# esquema-receptor.net
KiCad netlist of a schematic drawn in EAGLE
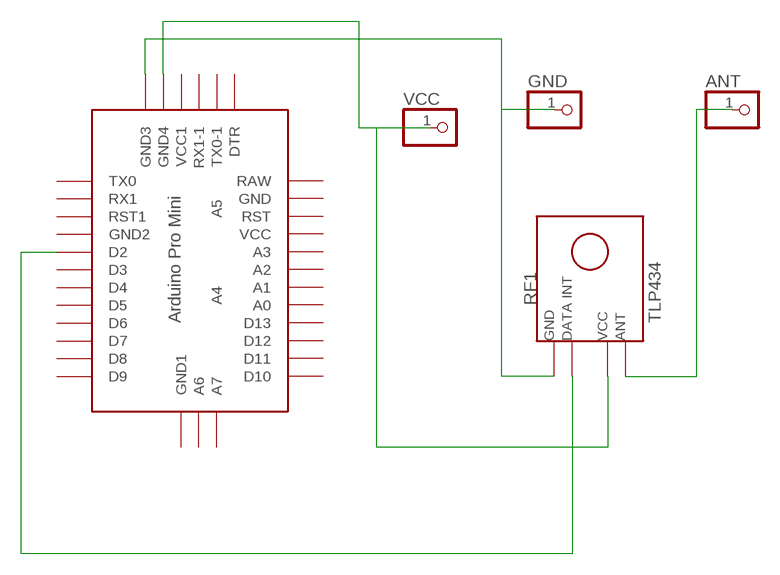
[diagram p0: schematic, sheet 1]

(export (version "E")
  (design (tool "Eeschema 10.0.6"))
  (components
    (comp (ref "ANT")
      (value "PINHD-1X1")
      (footprint "eagle-import:1X01")
      (libsource (lib "eagle-import") (part "PINHD-1X1"))
    )
    (comp (ref "GND")
      (value "PINHD-1X1")
      (footprint "eagle-import:1X01")
      (libsource (lib "eagle-import") (part "PINHD-1X1"))
    )
    (comp (ref "RF1")
      (value "TLP434")
      (footprint "eagle-import:TLP434")
      (libsource (lib "eagle-import") (part "TLP434"))
    )
    (comp (ref "U$1")
      (value "ABK-PRO-MINI")
      (footprint "eagle-import:ABK-PRO-MINI")
      (libsource (lib "eagle-import") (part "ABK-PRO-MINI"))
    )
    (comp (ref "VCC")
      (value "PINHD-1X1")
      (footprint "eagle-import:1X01")
      (libsource (lib "eagle-import") (part "PINHD-1X1"))
    )
  )
  (nets
    (net (code "1") (name "Net-(ANT-Pad1)") (class "Default")
      (node (ref "ANT") (pin "1") (pinfunction "1_1") (pintype "passive"))
      (node (ref "RF1") (pin "4") (pinfunction "4_4") (pintype "output"))
    )
    (net (code "2") (name "Net-(RF1-Pad2)") (class "Default")
      (node (ref "RF1") (pin "2") (pinfunction "2_2") (pintype "input"))
      (node (ref "U$1") (pin "D2") (pinfunction "D2_D2") (pintype "bidirectional"))
    )
    (net (code "3") (name "Net-(U$1-GND3)") (class "Default")
      (node (ref "GND") (pin "1") (pinfunction "1_1") (pintype "passive"))
      (node (ref "RF1") (pin "1") (pinfunction "1_1") (pintype "power_in"))
      (node (ref "U$1") (pin "GND2") (pinfunction "GND3_GND2") (pintype "bidirectional"))
    )
    (net (code "4") (name "Net-(U$1-GND4)") (class "Default")
      (node (ref "RF1") (pin "3") (pinfunction "3_3") (pintype "power_in"))
      (node (ref "U$1") (pin "GND3") (pinfunction "GND4_GND3") (pintype "bidirectional"))
      (node (ref "VCC") (pin "1") (pinfunction "1_1") (pintype "passive"))
    )
    (net (code "5") (name "unconnected-(U$1-GND1-PadGND4)") (class "Default")
      (node (ref "U$1") (pin "GND4") (pinfunction "GND1_GND4") (pintype "bidirectional"))
    )
    (net (code "6") (name "unconnected-(U$1-GND2-PadGND1)") (class "Default")
      (node (ref "U$1") (pin "GND1") (pinfunction "GND2_GND1") (pintype "bidirectional"))
    )
    (net (code "7") (name "unconnected-(U$1-PadA0)") (class "Default")
      (node (ref "U$1") (pin "A0") (pinfunction "A0_A0") (pintype "bidirectional"))
    )
    (net (code "8") (name "unconnected-(U$1-PadA1)") (class "Default")
      (node (ref "U$1") (pin "A1") (pinfunction "A1_A1") (pintype "bidirectional"))
    )
    (net (code "9") (name "unconnected-(U$1-PadA2)") (class "Default")
      (node (ref "U$1") (pin "A2") (pinfunction "A2_A2") (pintype "bidirectional"))
    )
    (net (code "10") (name "unconnected-(U$1-PadA3)") (class "Default")
      (node (ref "U$1") (pin "A3") (pinfunction "A3_A3") (pintype "bidirectional"))
    )
    (net (code "11") (name "unconnected-(U$1-PadA4)") (class "Default")
      (node (ref "U$1") (pin "A4") (pinfunction "A4_A4") (pintype "bidirectional"))
    )
    (net (code "12") (name "unconnected-(U$1-PadA5)") (class "Default")
      (node (ref "U$1") (pin "A5") (pinfunction "A5_A5") (pintype "bidirectional"))
    )
    (net (code "13") (name "unconnected-(U$1-PadA6)") (class "Default")
      (node (ref "U$1") (pin "A6") (pinfunction "A6_A6") (pintype "bidirectional"))
    )
    (net (code "14") (name "unconnected-(U$1-PadA7)") (class "Default")
      (node (ref "U$1") (pin "A7") (pinfunction "A7_A7") (pintype "bidirectional"))
    )
    (net (code "15") (name "unconnected-(U$1-PadD3)") (class "Default")
      (node (ref "U$1") (pin "D3") (pinfunction "D3_D3") (pintype "bidirectional"))
    )
    (net (code "16") (name "unconnected-(U$1-PadD4)") (class "Default")
      (node (ref "U$1") (pin "D4") (pinfunction "D4_D4") (pintype "bidirectional"))
    )
    (net (code "17") (name "unconnected-(U$1-PadD5)") (class "Default")
      (node (ref "U$1") (pin "D5") (pinfunction "D5_D5") (pintype "bidirectional"))
    )
    (net (code "18") (name "unconnected-(U$1-PadD6)") (class "Default")
      (node (ref "U$1") (pin "D6") (pinfunction "D6_D6") (pintype "bidirectional"))
    )
    (net (code "19") (name "unconnected-(U$1-PadD7)") (class "Default")
      (node (ref "U$1") (pin "D7") (pinfunction "D7_D7") (pintype "bidirectional"))
    )
    (net (code "20") (name "unconnected-(U$1-PadD8)") (class "Default")
      (node (ref "U$1") (pin "D8") (pinfunction "D8_D8") (pintype "bidirectional"))
    )
    (net (code "21") (name "unconnected-(U$1-PadD9)") (class "Default")
      (node (ref "U$1") (pin "D9") (pinfunction "D9_D9") (pintype "bidirectional"))
    )
    (net (code "22") (name "unconnected-(U$1-PadD10)") (class "Default")
      (node (ref "U$1") (pin "D10") (pinfunction "D10_D10") (pintype "bidirectional"))
    )
    (net (code "23") (name "unconnected-(U$1-PadD11)") (class "Default")
      (node (ref "U$1") (pin "D11") (pinfunction "D11_D11") (pintype "bidirectional"))
    )
    (net (code "24") (name "unconnected-(U$1-PadD12)") (class "Default")
      (node (ref "U$1") (pin "D12") (pinfunction "D12_D12") (pintype "bidirectional"))
    )
    (net (code "25") (name "unconnected-(U$1-PadD13)") (class "Default")
      (node (ref "U$1") (pin "D13") (pinfunction "D13_D13") (pintype "bidirectional"))
    )
    (net (code "26") (name "unconnected-(U$1-PadDTR)") (class "Default")
      (node (ref "U$1") (pin "DTR") (pinfunction "DTR_DTR") (pintype "bidirectional"))
    )
    (net (code "27") (name "unconnected-(U$1-PadGND)") (class "Default")
      (node (ref "U$1") (pin "GND") (pinfunction "GND_GND") (pintype "bidirectional"))
    )
    (net (code "28") (name "unconnected-(U$1-PadRAW)") (class "Default")
      (node (ref "U$1") (pin "RAW") (pinfunction "RAW_RAW") (pintype "bidirectional"))
    )
    (net (code "29") (name "unconnected-(U$1-PadRST)") (class "Default")
      (node (ref "U$1") (pin "RST") (pinfunction "RST_RST") (pintype "bidirectional"))
    )
    (net (code "30") (name "unconnected-(U$1-PadRST1)") (class "Default")
      (node (ref "U$1") (pin "RST1") (pinfunction "RST1_RST1") (pintype "bidirectional"))
    )
    (net (code "31") (name "unconnected-(U$1-PadRX1)") (class "Default")
      (node (ref "U$1") (pin "RX1") (pinfunction "RX1_RX1") (pintype "bidirectional"))
    )
    (net (code "32") (name "unconnected-(U$1-PadRX1-1)") (class "Default")
      (node (ref "U$1") (pin "RX1-1") (pinfunction "RX1-1_RX1-1") (pintype "bidirectional"))
    )
    (net (code "33") (name "unconnected-(U$1-PadTX0)") (class "Default")
      (node (ref "U$1") (pin "TX0") (pinfunction "TX0_TX0") (pintype "bidirectional"))
    )
    (net (code "34") (name "unconnected-(U$1-PadTX0-1)") (class "Default")
      (node (ref "U$1") (pin "TX0-1") (pinfunction "TX0-1_TX0-1") (pintype "bidirectional"))
    )
    (net (code "35") (name "unconnected-(U$1-PadVCC)") (class "Default")
      (node (ref "U$1") (pin "VCC") (pinfunction "VCC_VCC") (pintype "bidirectional"))
    )
    (net (code "36") (name "unconnected-(U$1-PadVCC1)") (class "Default")
      (node (ref "U$1") (pin "VCC1") (pinfunction "VCC1_VCC1") (pintype "bidirectional"))
    )
  )
)
